# 02_Top_Level.net
KiCad netlist of a schematic drawn in Altium Designer
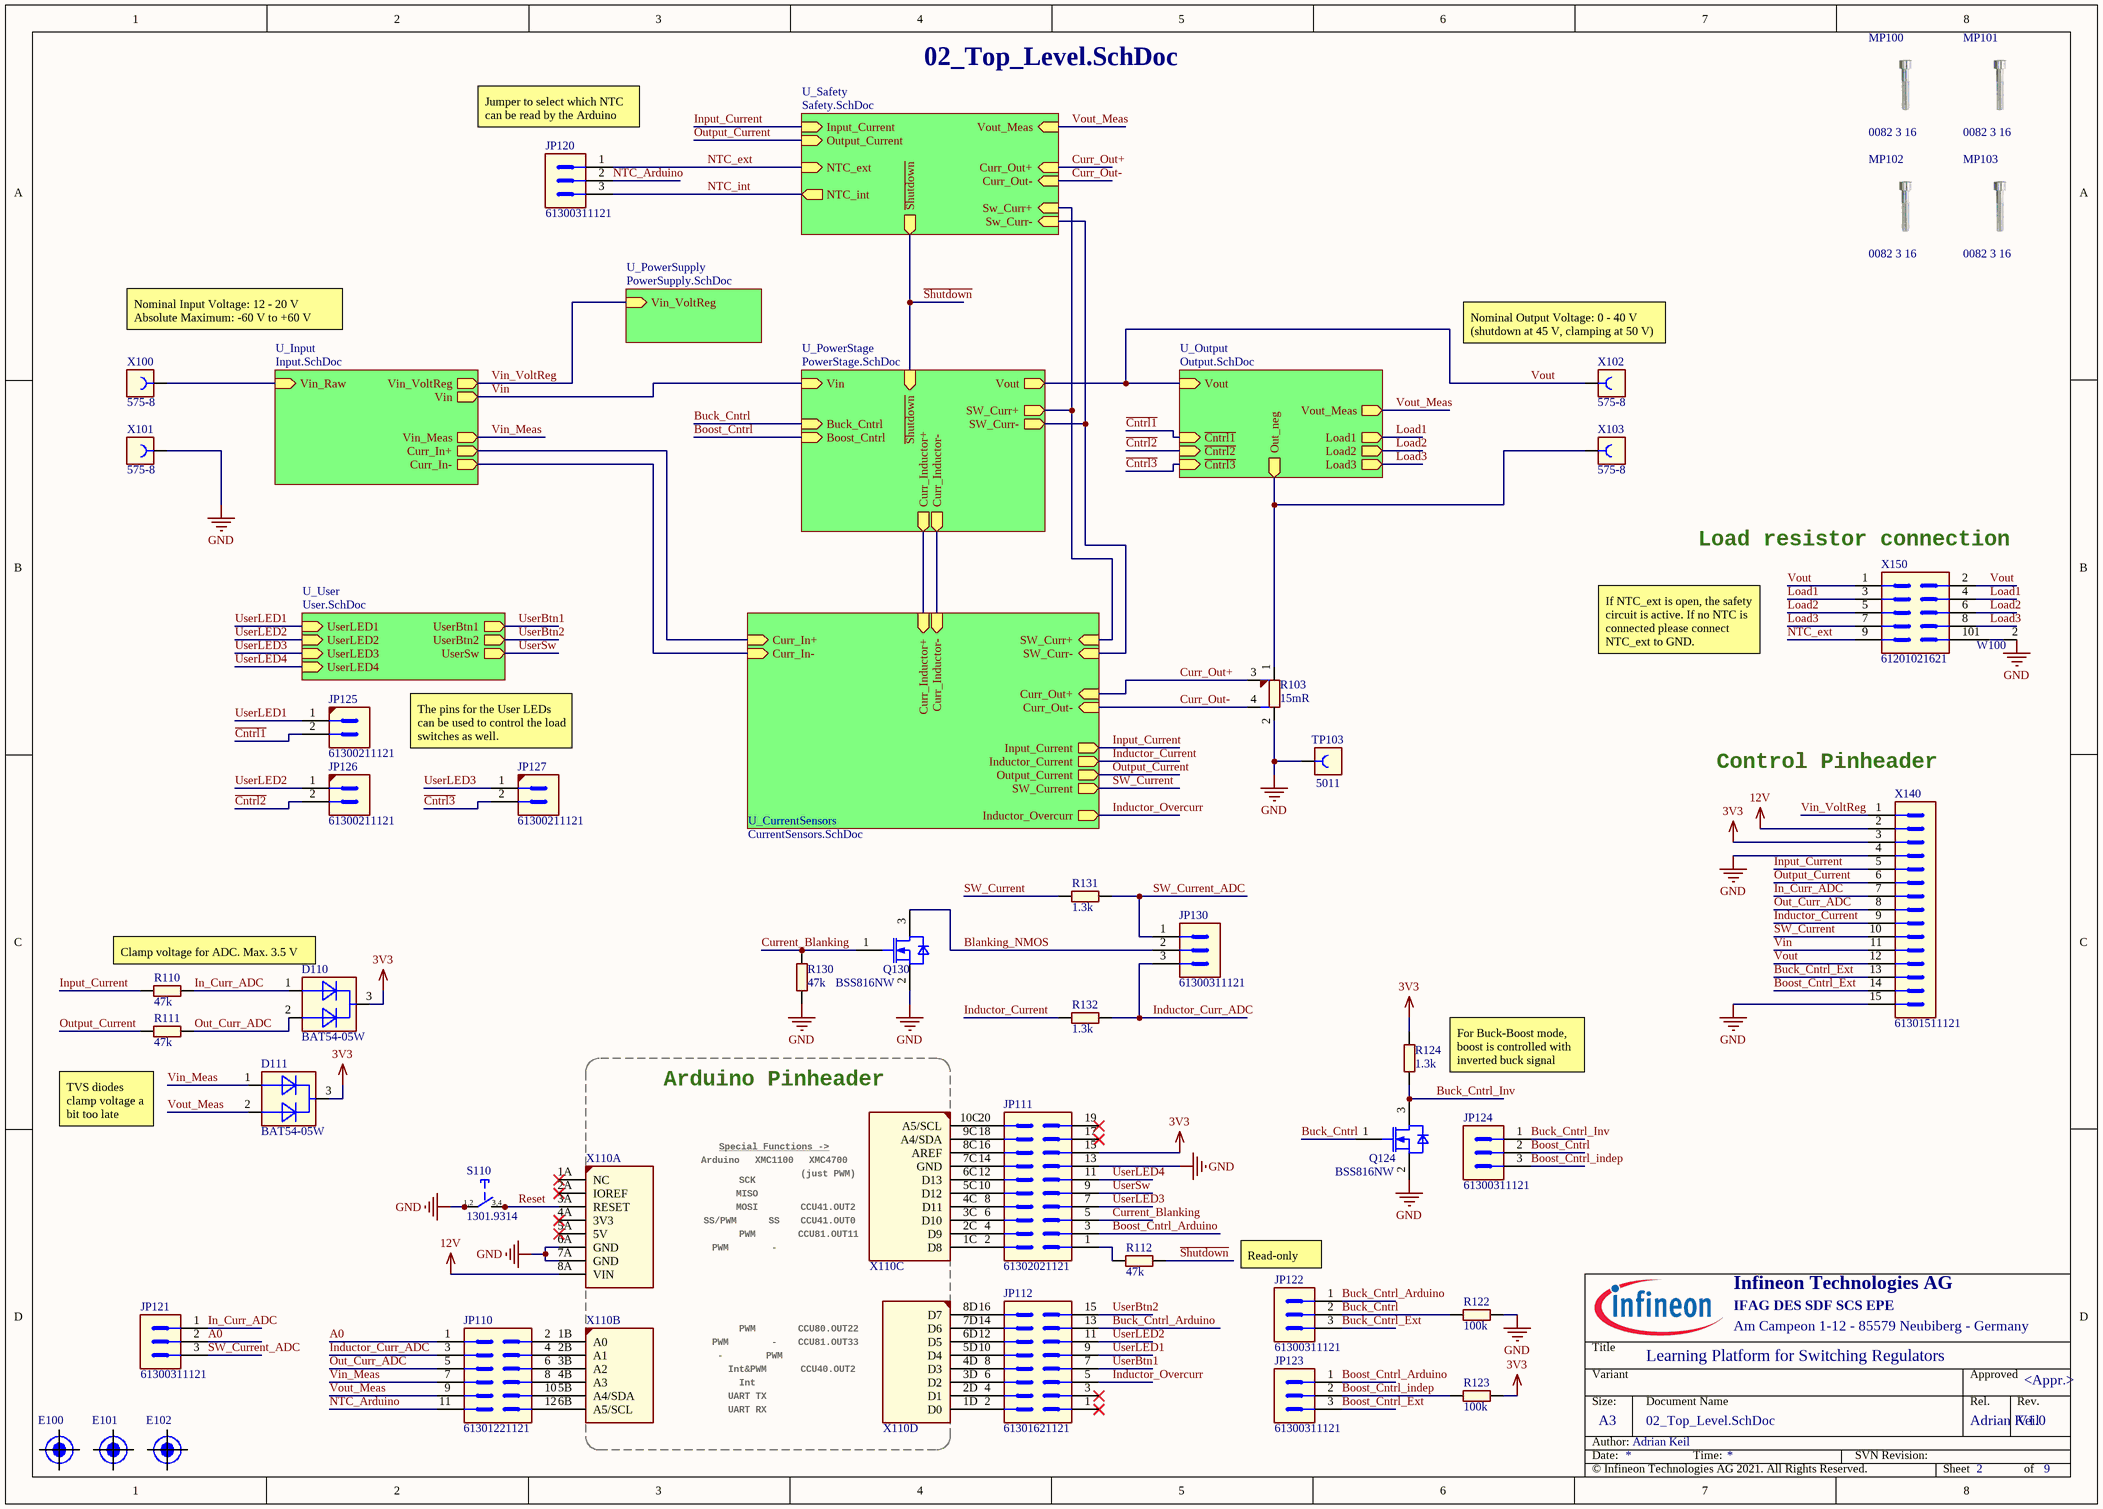
[diagram p0: 02_Top_Level.SchDoc]

(export (version "E")
  (design (tool "Eeschema 10.0.6"))
  (components
    (comp (ref "D110")
      (value "BAT54-05W")
      (footprint "SOT65P210X100-3N-1-V")
      (description "Silicon Schottky Diode, VR 30V")
      (fields (field (name "MANUFACTURER") "Infineon Technologies"))
      (libsource (lib "PCBLibraryData") (part "d_dual_a1a2c3_3p"))
    )
    (comp (ref "D111")
      (value "BAT54-05W")
      (footprint "SOT65P210X100-3N-1-V")
      (description "Silicon Schottky Diode, VR 30V")
      (fields (field (name "MANUFACTURER") "Infineon Technologies"))
      (libsource (lib "PCBLibraryData") (part "d_dual_a1a2c3_3p"))
    )
    (comp (ref "E100")
      (value "~")
      (footprint "fiducial")
      (description "Fiducial Mark")
      (fields
        (field (name "LEGACY PARTNUMBER") "MEC10000008")
        (field (name "MANUFACTURER") "Infineon Technologies")
      )
      (libsource (lib "PCBLibraryData") (part "fiducial"))
    )
    (comp (ref "E101")
      (value "~")
      (footprint "fiducial")
      (description "Fiducial Mark")
      (fields
        (field (name "LEGACY PARTNUMBER") "MEC10000008")
        (field (name "MANUFACTURER") "Infineon Technologies")
      )
      (libsource (lib "PCBLibraryData") (part "fiducial"))
    )
    (comp (ref "E102")
      (value "~")
      (footprint "fiducial")
      (description "Fiducial Mark")
      (fields
        (field (name "LEGACY PARTNUMBER") "MEC10000008")
        (field (name "MANUFACTURER") "Infineon Technologies")
      )
      (libsource (lib "PCBLibraryData") (part "fiducial"))
    )
    (comp (ref "JP110")
      (value "61301221121")
      (footprint "CON-M-THT-61301221121")
      (description "WR-PHD Dual Pin Header, 2.54mm Pitch, Double row, 12 Pins")
      (fields (field (name "MANUFACTURER") "Wurth Elektronik"))
      (libsource (lib "PCBLibraryData") (part "Header 6x2"))
    )
    (comp (ref "JP111")
      (value "61302021121")
      (footprint "CON-M-THT-61302021121")
      (description "WR-PHD Dual Pin Header, 2.54mm Pitch, Double row, 20 Pins")
      (fields (field (name "MANUFACTURER") "Wurth Elektronik"))
      (libsource (lib "PCBLibraryData") (part "Header 10X2"))
    )
    (comp (ref "JP112")
      (value "61301621121")
      (footprint "CON-M-THT-61301621121")
      (description "Connector Header Through Hole 16 position 0.100 (2.54mm)")
      (fields (field (name "MANUFACTURER") "Wurth Elektronik"))
      (libsource (lib "PCBLibraryData") (part "Header 8X2"))
    )
    (comp (ref "JP120")
      (value "61300311121")
      (footprint "CON-M-THT-61300311121")
      (description "WR-PHD Pin Header")
      (fields (field (name "MANUFACTURER") "Wurth Elektronik"))
      (libsource (lib "PCBLibraryData") (part "Header 3"))
    )
    (comp (ref "JP121")
      (value "61300311121")
      (footprint "CON-M-THT-61300311121")
      (description "WR-PHD Pin Header")
      (fields (field (name "MANUFACTURER") "Wurth Elektronik"))
      (libsource (lib "PCBLibraryData") (part "Header 3"))
    )
    (comp (ref "JP122")
      (value "61300311121")
      (footprint "CON-M-THT-61300311121")
      (description "WR-PHD Pin Header")
      (fields (field (name "MANUFACTURER") "Wurth Elektronik"))
      (libsource (lib "PCBLibraryData") (part "Header 3"))
    )
    (comp (ref "JP123")
      (value "61300311121")
      (footprint "CON-M-THT-61300311121")
      (description "WR-PHD Pin Header")
      (fields (field (name "MANUFACTURER") "Wurth Elektronik"))
      (libsource (lib "PCBLibraryData") (part "Header 3"))
    )
    (comp (ref "JP124")
      (value "61300311121")
      (footprint "CON-M-THT-61300311121")
      (description "WR-PHD Pin Header")
      (fields (field (name "MANUFACTURER") "Wurth Elektronik"))
      (libsource (lib "PCBLibraryData") (part "Header 3"))
    )
    (comp (ref "JP125")
      (value "61300211121")
      (footprint "CON-M-THT-61300211121")
      (description "Header, 2.54mm Pitch, 2 pin, Vertical, Single Row")
      (fields
        (field (name "LEGACY PARTNUMBER") "CON01500943")
        (field (name "MANUFACTURER") "Wurth Elektronik")
      )
      (libsource (lib "PCBLibraryData") (part "Header 2"))
    )
    (comp (ref "JP126")
      (value "61300211121")
      (footprint "CON-M-THT-61300211121")
      (description "Header, 2.54mm Pitch, 2 pin, Vertical, Single Row")
      (fields
        (field (name "LEGACY PARTNUMBER") "CON01500943")
        (field (name "MANUFACTURER") "Wurth Elektronik")
      )
      (libsource (lib "PCBLibraryData") (part "Header 2"))
    )
    (comp (ref "JP127")
      (value "61300211121")
      (footprint "CON-M-THT-61300211121")
      (description "Header, 2.54mm Pitch, 2 pin, Vertical, Single Row")
      (fields
        (field (name "LEGACY PARTNUMBER") "CON01500943")
        (field (name "MANUFACTURER") "Wurth Elektronik")
      )
      (libsource (lib "PCBLibraryData") (part "Header 2"))
    )
    (comp (ref "JP130")
      (value "61300311121")
      (footprint "CON-M-THT-61300311121")
      (description "WR-PHD Pin Header")
      (fields (field (name "MANUFACTURER") "Wurth Elektronik"))
      (libsource (lib "") (part "Header 3_1"))
    )
    (comp (ref "MP100")
      (value "0082 3 16")
      (footprint "SCREW_0082 3 16_NPTH")
      (description "Cheese Head Screw With Hexagon Socket, DIN 912 (ISO 4762), M3, 16mm length")
      (fields
        (field (name "LEGACY PARTNUMBER") "MEC10000167")
        (field (name "MANUFACTURER") "Wurth Elektronik")
      )
      (libsource (lib "PCBLibraryData") (part "Screw_0082 3 16"))
    )
    (comp (ref "MP101")
      (value "0082 3 16")
      (footprint "SCREW_0082 3 16_NPTH")
      (description "Cheese Head Screw With Hexagon Socket, DIN 912 (ISO 4762), M3, 16mm length")
      (fields
        (field (name "LEGACY PARTNUMBER") "MEC10000167")
        (field (name "MANUFACTURER") "Wurth Elektronik")
      )
      (libsource (lib "PCBLibraryData") (part "Screw_0082 3 16"))
    )
    (comp (ref "MP102")
      (value "0082 3 16")
      (footprint "SCREW_0082 3 16_NPTH")
      (description "Cheese Head Screw With Hexagon Socket, DIN 912 (ISO 4762), M3, 16mm length")
      (fields
        (field (name "LEGACY PARTNUMBER") "MEC10000167")
        (field (name "MANUFACTURER") "Wurth Elektronik")
      )
      (libsource (lib "PCBLibraryData") (part "Screw_0082 3 16"))
    )
    (comp (ref "MP103")
      (value "0082 3 16")
      (footprint "SCREW_0082 3 16_NPTH")
      (description "Cheese Head Screw With Hexagon Socket, DIN 912 (ISO 4762), M3, 16mm length")
      (fields
        (field (name "LEGACY PARTNUMBER") "MEC10000167")
        (field (name "MANUFACTURER") "Wurth Elektronik")
      )
      (libsource (lib "PCBLibraryData") (part "Screw_0082 3 16"))
    )
    (comp (ref "Q124")
      (value "BSS816NW")
      (footprint "SOT65P210X100-3N-1-V")
      (description "OptiMOS 2 Small-Signal-Transistor")
      (fields (field (name "MANUFACTURER") "Infineon Technologies"))
      (libsource (lib "PCBLibraryData") (part "igfet_n_ch_dep_dio_1g2s3d_3p"))
    )
    (comp (ref "Q130")
      (value "BSS816NW")
      (footprint "SOT65P210X100-3N-1-V")
      (description "OptiMOS 2 Small-Signal-Transistor")
      (fields (field (name "MANUFACTURER") "Infineon Technologies"))
      (libsource (lib "PCBLibraryData") (part "igfet_n_ch_dep_dio_1g2s3d_3p"))
    )
    (comp (ref "R103")
      (value "15mR")
      (footprint "RES-SMD-L4T12")
      (description "RES / STD / 15mR / 500mW / 1% / 75ppm/K / -55°C to 155°C / 1206 (3216) / SMD / -")
      (fields (field (name "MANUFACTURER") "Ohmite"))
      (libsource (lib "PCBLibraryData") (part "RES-SHT-STD-04P_00097BE5"))
    )
    (comp (ref "R110")
      (value "47k")
      (footprint "RESC1609X50N")
      (description "RES / STD / 47k / 100mW / 1% / 100ppm/K / -55°C to 155°C / 0603 / SMD / -")
      (fields (field (name "LEGACY PARTNUMBER") "RES01801333") (field (name "MANUFACTURER") "Vishay"))
      (libsource (lib "PCBLibraryData") (part "RES-SGL-STD-02P_00000006"))
    )
    (comp (ref "R111")
      (value "47k")
      (footprint "RESC1609X50N")
      (description "RES / STD / 47k / 100mW / 1% / 100ppm/K / -55°C to 155°C / 0603 / SMD / -")
      (fields (field (name "LEGACY PARTNUMBER") "RES01801333") (field (name "MANUFACTURER") "Vishay"))
      (libsource (lib "PCBLibraryData") (part "RES-SGL-STD-02P_00000006"))
    )
    (comp (ref "R112")
      (value "47k")
      (footprint "RESC1609X50N")
      (description "RES / STD / 47k / 100mW / 1% / 100ppm/K / -55°C to 155°C / 0603 / SMD / -")
      (fields (field (name "LEGACY PARTNUMBER") "RES01801333") (field (name "MANUFACTURER") "Vishay"))
      (libsource (lib "PCBLibraryData") (part "RES-SGL-STD-02P_00000006"))
    )
    (comp (ref "R122")
      (value "100k")
      (footprint "RESC1609X50N")
      (description "RES / STD / 100k / 100mW / 1% / 100ppm/K / -55°C to 155°C / 0603 / SMD / -")
      (fields (field (name "LEGACY PARTNUMBER") "RES01801371") (field (name "MANUFACTURER") "Vishay"))
      (libsource (lib "PCBLibraryData") (part "RES-SGL-STD-02P_00000006"))
    )
    (comp (ref "R123")
      (value "100k")
      (footprint "RESC1609X50N")
      (description "RES / STD / 100k / 100mW / 1% / 100ppm/K / -55°C to 155°C / 0603 / SMD / -")
      (fields (field (name "LEGACY PARTNUMBER") "RES01801371") (field (name "MANUFACTURER") "Vishay"))
      (libsource (lib "PCBLibraryData") (part "RES-SGL-STD-02P_00000006"))
    )
    (comp (ref "R124")
      (value "1.3k")
      (footprint "RESC1609X50N")
      (description "RES / STD / 1.3k / 100mW / 1% / 100ppm/K / -55°C to 155°C / 0603 / SMD / -")
      (fields (field (name "LEGACY PARTNUMBER") "RES01801155") (field (name "MANUFACTURER") "Vishay"))
      (libsource (lib "") (part "RES-SGL-STD-02P_00000006_1"))
    )
    (comp (ref "R130")
      (value "47k")
      (footprint "RESC1609X50N")
      (description "RES / STD / 47k / 100mW / 1% / 100ppm/K / -55°C to 155°C / 0603 / SMD / -")
      (fields (field (name "LEGACY PARTNUMBER") "RES01801333") (field (name "MANUFACTURER") "Vishay"))
      (libsource (lib "") (part "RES-SGL-STD-02P_00000006_1"))
    )
    (comp (ref "R131")
      (value "1.3k")
      (footprint "RESC1609X50N")
      (description "RES / STD / 1.3k / 100mW / 1% / 100ppm/K / -55°C to 155°C / 0603 / SMD / -")
      (fields (field (name "LEGACY PARTNUMBER") "RES01801155") (field (name "MANUFACTURER") "Vishay"))
      (libsource (lib "PCBLibraryData") (part "RES-SGL-STD-02P_00000006"))
    )
    (comp (ref "R132")
      (value "1.3k")
      (footprint "RESC1609X50N")
      (description "RES / STD / 1.3k / 100mW / 1% / 100ppm/K / -55°C to 155°C / 0603 / SMD / -")
      (fields (field (name "LEGACY PARTNUMBER") "RES01801155") (field (name "MANUFACTURER") "Vishay"))
      (libsource (lib "PCBLibraryData") (part "RES-SGL-STD-02P_00000006"))
    )
    (comp (ref "S110")
      (value "1301.9314")
      (footprint "SW-SMD-1301.9314")
      (description "Pushbutton Tactile Switch, Single Pole Single Throw, 4 Pins")
      (fields (field (name "LEGACY PARTNUMBER") "CON01500305") (field (name "MANUFACTURER") "Schurter"))
      (libsource (lib "PCBLibraryData") (part "sw_sr_no12_34_4p"))
    )
    (comp (ref "TP103")
      (value "5011")
      (footprint "CON-THT-TP-5011")
      (description "PC Test Point-Multipurpose THT, Black")
      (fields
        (field (name "LEGACY PARTNUMBER") "CON01500530")
        (field (name "MANUFACTURER") "Keystone Electronics Corp.")
      )
      (libsource (lib "") (part "connector_1_f_1"))
    )
    (comp (ref "W100")
      (value "Net_Tie_2")
      (footprint "Net_Tie_Small_2P")
      (description "SMD Net Tie for two Nets")
      (fields
        (field (name "LEGACY PARTNUMBER") "CON01501379")
        (field (name "MANUFACTURER") "Infineon Technologies")
      )
      (libsource (lib "PCBLibraryData") (part "Net_Tie_2"))
    )
    (comp (ref "X100")
      (value "575-8")
      (footprint "CON-F-TH-575-6")
      (description "Non Insulated Jack, Brass")
      (fields (field (name "MANUFACTURER") "Keystone Electronics Corp."))
      (libsource (lib "PCBLibraryData") (part "connector_1_f"))
    )
    (comp (ref "X101")
      (value "575-8")
      (footprint "CON-F-TH-575-6")
      (description "Non Insulated Jack, Brass")
      (fields (field (name "MANUFACTURER") "Keystone Electronics Corp."))
      (libsource (lib "PCBLibraryData") (part "connector_1_f"))
    )
    (comp (ref "X102")
      (value "575-8")
      (footprint "CON-F-TH-575-6")
      (description "Non Insulated Jack, Brass")
      (fields (field (name "MANUFACTURER") "Keystone Electronics Corp."))
      (libsource (lib "") (part "connector_1_f_2"))
    )
    (comp (ref "X103")
      (value "575-8")
      (footprint "CON-F-TH-575-6")
      (description "Non Insulated Jack, Brass")
      (fields (field (name "MANUFACTURER") "Keystone Electronics Corp."))
      (libsource (lib "") (part "connector_1_f_2"))
    )
    (comp (ref "X110")
      (value "Arduino-Uno")
      (footprint "Arduino-Uno")
      (description "Arduino Uno is a microcontroller board based on the ATmega328P")
      (fields (field (name "MANUFACTURER") "Infineon Technologies"))
      (libsource (lib "") (part "Arduino-Uno_1"))
    )
    (comp (ref "X140")
      (value "61301511121")
      (footprint "CON-M-THT-61301511121")
      (description "WR-PHD Pin Header, 2.54mm Pitch, Single row, 15 Pins")
      (fields (field (name "MANUFACTURER") "Wurth Elektronik"))
      (libsource (lib "PCBLibraryData") (part "Header 15"))
    )
    (comp (ref "X150")
      (value "61201021621")
      (footprint "CON-M-THT-61201021621")
      (description "WR-BHD Male Box Header, 2.54mm pitch, 10 pin, Vertical, Double row")
      (fields (field (name "MANUFACTURER") "Wurth Elektronik"))
      (libsource (lib "PCBLibraryData") (part "Header 5X2"))
    )
  )
  (nets
    (net (code "1") (name "/A0") (class "Default")
      (node (ref "JP110") (pin "1") (pinfunction "1_1") (pintype "passive"))
      (node (ref "JP121") (pin "2") (pinfunction "2_2") (pintype "passive"))
    )
    (net (code "2") (name "/Blanking_NMOS") (class "Default")
      (node (ref "JP130") (pin "2") (pinfunction "2_2") (pintype "passive"))
      (node (ref "Q130") (pin "3") (pinfunction "DRAIN_3") (pintype "passive"))
    )
    (net (code "3") (name "/Boost_Cntrl") (class "Default")
      (node (ref "JP124") (pin "2") (pinfunction "2_2") (pintype "passive"))
    )
    (net (code "4") (name "/Boost_Cntrl_Arduino") (class "Default")
      (node (ref "JP111") (pin "3") (pinfunction "3_3") (pintype "passive"))
      (node (ref "JP123") (pin "1") (pinfunction "1_1") (pintype "passive"))
    )
    (net (code "5") (name "/Boost_Cntrl_Ext") (class "Default")
      (node (ref "JP123") (pin "3") (pinfunction "3_3") (pintype "passive"))
      (node (ref "X140") (pin "14") (pinfunction "14_14") (pintype "passive"))
    )
    (net (code "6") (name "/Boost_Cntrl_indep") (class "Default")
      (node (ref "JP123") (pin "2") (pinfunction "2_2") (pintype "passive"))
      (node (ref "JP124") (pin "3") (pinfunction "3_3") (pintype "passive"))
      (node (ref "R123") (pin "2") (pinfunction "2_2") (pintype "passive"))
    )
    (net (code "7") (name "/Buck_Cntrl") (class "Default")
      (node (ref "JP122") (pin "2") (pinfunction "2_2") (pintype "passive"))
      (node (ref "Q124") (pin "1") (pinfunction "GATE_1") (pintype "passive"))
      (node (ref "R122") (pin "2") (pinfunction "2_2") (pintype "passive"))
    )
    (net (code "8") (name "/Buck_Cntrl_Arduino") (class "Default")
      (node (ref "JP112") (pin "13") (pinfunction "13_13") (pintype "passive"))
      (node (ref "JP122") (pin "1") (pinfunction "1_1") (pintype "passive"))
    )
    (net (code "9") (name "/Buck_Cntrl_Ext") (class "Default")
      (node (ref "JP122") (pin "3") (pinfunction "3_3") (pintype "passive"))
      (node (ref "X140") (pin "13") (pinfunction "13_13") (pintype "passive"))
    )
    (net (code "10") (name "/Buck_Cntrl_Inv") (class "Default")
      (node (ref "JP124") (pin "1") (pinfunction "1_1") (pintype "passive"))
      (node (ref "Q124") (pin "3") (pinfunction "DRAIN_3") (pintype "passive"))
      (node (ref "R124") (pin "1") (pinfunction "1_1") (pintype "passive"))
    )
    (net (code "11") (name "/Cntrl1") (class "Default")
      (node (ref "JP125") (pin "2") (pinfunction "2_2") (pintype "passive"))
    )
    (net (code "12") (name "/Cntrl2") (class "Default")
      (node (ref "JP126") (pin "2") (pinfunction "2_2") (pintype "passive"))
    )
    (net (code "13") (name "/Cntrl3") (class "Default")
      (node (ref "JP127") (pin "2") (pinfunction "2_2") (pintype "passive"))
    )
    (net (code "18") (name "/Curr_Out+") (class "Default")
      (node (ref "R103") (pin "3") (pinfunction "I1_3") (pintype "passive"))
    )
    (net (code "19") (name "/Curr_Out-") (class "Default")
      (node (ref "R103") (pin "4") (pinfunction "I2_4") (pintype "passive"))
    )
    (net (code "20") (name "/Current_Blanking") (class "Default")
      (node (ref "JP111") (pin "5") (pinfunction "5_5") (pintype "passive"))
      (node (ref "Q130") (pin "1") (pinfunction "GATE_1") (pintype "passive"))
      (node (ref "R130") (pin "2") (pinfunction "2_2") (pintype "passive"))
    )
    (net (code "21") (name "/In_Curr_ADC") (class "Default")
      (node (ref "D110") (pin "1") (pinfunction "ANODE_1_1") (pintype "passive"))
      (node (ref "JP121") (pin "1") (pinfunction "1_1") (pintype "passive"))
      (node (ref "R110") (pin "1") (pinfunction "1_1") (pintype "passive"))
      (node (ref "X140") (pin "7") (pinfunction "7_7") (pintype "passive"))
    )
    (net (code "22") (name "/Inductor_Curr_ADC") (class "Default")
      (node (ref "JP110") (pin "3") (pinfunction "3_3") (pintype "passive"))
      (node (ref "JP130") (pin "3") (pinfunction "3_3") (pintype "passive"))
      (node (ref "R132") (pin "1") (pinfunction "1_1") (pintype "passive"))
    )
    (net (code "23") (name "/Inductor_Current") (class "Default")
      (node (ref "R132") (pin "2") (pinfunction "2_2") (pintype "passive"))
      (node (ref "X140") (pin "9") (pinfunction "9_9") (pintype "passive"))
    )
    (net (code "24") (name "/Inductor_Overcurr") (class "Default")
      (node (ref "JP112") (pin "5") (pinfunction "5_5") (pintype "passive"))
    )
    (net (code "25") (name "/Input_Current") (class "Default")
      (node (ref "R110") (pin "2") (pinfunction "2_2") (pintype "passive"))
      (node (ref "X140") (pin "5") (pinfunction "5_5") (pintype "passive"))
    )
    (net (code "26") (name "/Load1") (class "Default")
      (node (ref "X150") (pin "3") (pinfunction "3_3") (pintype "passive"))
      (node (ref "X150") (pin "4") (pinfunction "4_4") (pintype "passive"))
    )
    (net (code "27") (name "/Load2") (class "Default")
      (node (ref "X150") (pin "5") (pinfunction "5_5") (pintype "passive"))
      (node (ref "X150") (pin "6") (pinfunction "6_6") (pintype "passive"))
    )
    (net (code "28") (name "/Load3") (class "Default")
      (node (ref "X150") (pin "7") (pinfunction "7_7") (pintype "passive"))
      (node (ref "X150") (pin "8") (pinfunction "8_8") (pintype "passive"))
    )
    (net (code "29") (name "/NTC_Arduino") (class "Default")
      (node (ref "JP110") (pin "11") (pinfunction "11_11") (pintype "passive"))
      (node (ref "JP120") (pin "2") (pinfunction "2_2") (pintype "passive"))
    )
    (net (code "30") (name "/NTC_ext") (class "Default")
      (node (ref "JP120") (pin "1") (pinfunction "1_1") (pintype "passive"))
      (node (ref "X150") (pin "9") (pinfunction "9_9") (pintype "passive"))
    )
    (net (code "31") (name "/NTC_int") (class "Default")
      (node (ref "JP120") (pin "3") (pinfunction "3_3") (pintype "passive"))
    )
    (net (code "32") (name "/Out_Curr_ADC") (class "Default")
      (node (ref "D110") (pin "2") (pinfunction "ANODE_2_2") (pintype "passive"))
      (node (ref "JP110") (pin "5") (pinfunction "5_5") (pintype "passive"))
      (node (ref "R111") (pin "1") (pinfunction "1_1") (pintype "passive"))
      (node (ref "X140") (pin "8") (pinfunction "8_8") (pintype "passive"))
    )
    (net (code "33") (name "/Out_neg") (class "Default")
      (node (ref "R103") (pin "1") (pinfunction "V1_1") (pintype "passive"))
      (node (ref "X103") (pin "1") (pinfunction "1_1") (pintype "passive"))
    )
    (net (code "34") (name "/Output_Current") (class "Default")
      (node (ref "R111") (pin "2") (pinfunction "2_2") (pintype "passive"))
      (node (ref "X140") (pin "6") (pinfunction "6_6") (pintype "passive"))
    )
    (net (code "35") (name "/Reset") (class "Default")
      (node (ref "S110") (pin "3") (pinfunction "3_3") (pintype "passive"))
      (node (ref "S110") (pin "4") (pinfunction "4_4") (pintype "passive"))
      (node (ref "X110") (pin "3A") (pinfunction "RESET_3A") (pintype "passive"))
    )
    (net (code "38") (name "/SW_Current") (class "Default")
      (node (ref "R131") (pin "2") (pinfunction "2_2") (pintype "passive"))
      (node (ref "X140") (pin "10") (pinfunction "10_10") (pintype "passive"))
    )
    (net (code "39") (name "/SW_Current_ADC") (class "Default")
      (node (ref "JP121") (pin "3") (pinfunction "3_3") (pintype "passive"))
      (node (ref "JP130") (pin "1") (pinfunction "1_1") (pintype "passive"))
      (node (ref "R131") (pin "1") (pinfunction "1_1") (pintype "passive"))
    )
    (net (code "40") (name "/Shutdown") (class "Default")
      (node (ref "R112") (pin "1") (pinfunction "1_1") (pintype "passive"))
    )
    (net (code "41") (name "/UserBtn1") (class "Default")
      (node (ref "JP112") (pin "7") (pinfunction "7_7") (pintype "passive"))
    )
    (net (code "42") (name "/UserBtn2") (class "Default")
      (node (ref "JP112") (pin "15") (pinfunction "15_15") (pintype "passive"))
    )
    (net (code "43") (name "/UserLED1") (class "Default")
      (node (ref "JP112") (pin "9") (pinfunction "9_9") (pintype "passive"))
      (node (ref "JP125") (pin "1") (pinfunction "1_1") (pintype "passive"))
    )
    (net (code "44") (name "/UserLED2") (class "Default")
      (node (ref "JP112") (pin "11") (pinfunction "11_11") (pintype "passive"))
      (node (ref "JP126") (pin "1") (pinfunction "1_1") (pintype "passive"))
    )
    (net (code "45") (name "/UserLED3") (class "Default")
      (node (ref "JP111") (pin "7") (pinfunction "7_7") (pintype "passive"))
      (node (ref "JP127") (pin "1") (pinfunction "1_1") (pintype "passive"))
    )
    (net (code "46") (name "/UserLED4") (class "Default")
      (node (ref "JP111") (pin "11") (pinfunction "11_11") (pintype "passive"))
    )
    (net (code "47") (name "/UserSw") (class "Default")
      (node (ref "JP111") (pin "9") (pinfunction "9_9") (pintype "passive"))
    )
    (net (code "48") (name "/Vin") (class "Default")
      (node (ref "X140") (pin "11") (pinfunction "11_11") (pintype "passive"))
    )
    (net (code "49") (name "/Vin_Meas") (class "Default")
      (node (ref "D111") (pin "1") (pinfunction "ANODE_1_1") (pintype "passive"))
      (node (ref "JP110") (pin "7") (pinfunction "7_7") (pintype "passive"))
    )
    (net (code "50") (name "/Vin_Raw") (class "Default")
      (node (ref "X100") (pin "1") (pinfunction "1_1") (pintype "passive"))
    )
    (net (code "51") (name "/Vin_VoltReg") (class "Default")
      (node (ref "X140") (pin "1") (pinfunction "1_1") (pintype "passive"))
    )
    (net (code "52") (name "/Vout") (class "Default")
      (node (ref "X102") (pin "1") (pinfunction "1_1") (pintype "passive"))
      (node (ref "X140") (pin "12") (pinfunction "12_12") (pintype "passive"))
      (node (ref "X150") (pin "1") (pinfunction "1_1") (pintype "passive"))
      (node (ref "X150") (pin "2") (pinfunction "2_2") (pintype "passive"))
    )
    (net (code "53") (name "/Vout_Meas") (class "Default")
      (node (ref "D111") (pin "2") (pinfunction "ANODE_2_2") (pintype "passive"))
      (node (ref "JP110") (pin "9") (pinfunction "9_9") (pintype "passive"))
    )
    (net (code "54") (name "3V3") (class "Default")
      (node (ref "D110") (pin "3") (pinfunction "CATHODE_3") (pintype "passive"))
      (node (ref "D111") (pin "3") (pinfunction "CATHODE_3") (pintype "passive"))
      (node (ref "JP111") (pin "15") (pinfunction "15_15") (pintype "passive"))
      (node (ref "R123") (pin "1") (pinfunction "1_1") (pintype "passive"))
      (node (ref "R124") (pin "2") (pinfunction "2_2") (pintype "passive"))
      (node (ref "X140") (pin "3") (pinfunction "3_3") (pintype "passive"))
    )
    (net (code "55") (name "12V") (class "Default")
      (node (ref "X110") (pin "8A") (pinfunction "VIN_8A") (pintype "passive"))
      (node (ref "X140") (pin "2") (pinfunction "2_2") (pintype "passive"))
    )
    (net (code "56") (name "GND") (class "Default")
      (node (ref "JP111") (pin "13") (pinfunction "13_13") (pintype "passive"))
      (node (ref "Q124") (pin "2") (pinfunction "SOURCE_2") (pintype "passive"))
      (node (ref "Q130") (pin "2") (pinfunction "SOURCE_2") (pintype "passive"))
      (node (ref "R103") (pin "2") (pinfunction "V2_2") (pintype "passive"))
      (node (ref "R122") (pin "1") (pinfunction "1_1") (pintype "passive"))
      (node (ref "R130") (pin "1") (pinfunction "1_1") (pintype "passive"))
      (node (ref "S110") (pin "1") (pinfunction "1_1") (pintype "passive"))
      (node (ref "S110") (pin "2") (pinfunction "2_2") (pintype "passive"))
      (node (ref "TP103") (pin "1") (pinfunction "1_1") (pintype "passive"))
      (node (ref "W100") (pin "2") (pinfunction "2_2") (pintype "passive"))
      (node (ref "X101") (pin "1") (pinfunction "1_1") (pintype "passive"))
      (node (ref "X110") (pin "6A") (pinfunction "GND_6A") (pintype "passive"))
      (node (ref "X110") (pin "7A") (pinfunction "GND_7A") (pintype "passive"))
      (node (ref "X140") (pin "15") (pinfunction "15_15") (pintype "passive"))
      (node (ref "X140") (pin "4") (pinfunction "4_4") (pintype "passive"))
    )
    (net (code "57") (name "Net-(JP111-Pad1)") (class "Default")
      (node (ref "JP111") (pin "1") (pinfunction "1_1") (pintype "passive"))
      (node (ref "R112") (pin "2") (pinfunction "2_2") (pintype "passive"))
    )
    (net (code "58") (name "Net-(W100-Pad1)") (class "Default")
      (node (ref "W100") (pin "1") (pinfunction "1_1") (pintype "passive"))
      (node (ref "X150") (pin "10") (pinfunction "10_10") (pintype "passive"))
    )
    (net (code "59") (name "Net-(X110B-A0)") (class "Default")
      (node (ref "JP110") (pin "2") (pinfunction "2_2") (pintype "passive"))
      (node (ref "X110") (pin "1B") (pinfunction "A0_1B") (pintype "passive"))
    )
    (net (code "60") (name "Net-(X110B-A1)") (class "Default")
      (node (ref "JP110") (pin "4") (pinfunction "4_4") (pintype "passive"))
      (node (ref "X110") (pin "2B") (pinfunction "A1_2B") (pintype "passive"))
    )
    (net (code "61") (name "Net-(X110B-A2)") (class "Default")
      (node (ref "JP110") (pin "6") (pinfunction "6_6") (pintype "passive"))
      (node (ref "X110") (pin "3B") (pinfunction "A2_3B") (pintype "passive"))
    )
    (net (code "62") (name "Net-(X110B-A3)") (class "Default")
      (node (ref "JP110") (pin "8") (pinfunction "8_8") (pintype "passive"))
      (node (ref "X110") (pin "4B") (pinfunction "A3_4B") (pintype "passive"))
    )
    (net (code "63") (name "Net-(X110B-A4{slash}SDA)") (class "Default")
      (node (ref "JP110") (pin "10") (pinfunction "10_10") (pintype "passive"))
      (node (ref "X110") (pin "5B") (pinfunction "A4/SDA_5B") (pintype "passive"))
    )
    (net (code "64") (name "Net-(X110B-A5{slash}SCL)") (class "Default")
      (node (ref "JP110") (pin "12") (pinfunction "12_12") (pintype "passive"))
      (node (ref "X110") (pin "6B") (pinfunction "A5/SCL_6B") (pintype "passive"))
    )
    (net (code "65") (name "Net-(X110C-A4{slash}SDA)") (class "Default")
      (node (ref "JP111") (pin "18") (pinfunction "18_18") (pintype "passive"))
      (node (ref "X110") (pin "9C") (pinfunction "A4/SDA_9C") (pintype "passive"))
    )
    (net (code "66") (name "Net-(X110C-A5{slash}SCL)") (class "Default")
      (node (ref "JP111") (pin "20") (pinfunction "20_20") (pintype "passive"))
      (node (ref "X110") (pin "10C") (pinfunction "A5/SCL_10C") (pintype "passive"))
    )
    (net (code "67") (name "Net-(X110C-AREF)") (class "Default")
      (node (ref "JP111") (pin "16") (pinfunction "16_16") (pintype "passive"))
      (node (ref "X110") (pin "8C") (pinfunction "AREF_8C") (pintype "passive"))
    )
    (net (code "68") (name "Net-(X110C-D8)") (class "Default")
      (node (ref "JP111") (pin "2") (pinfunction "2_2") (pintype "passive"))
      (node (ref "X110") (pin "1C") (pinfunction "D8_1C") (pintype "passive"))
    )
    (net (code "69") (name "Net-(X110C-D9)") (class "Default")
      (node (ref "JP111") (pin "4") (pinfunction "4_4") (pintype "passive"))
      (node (ref "X110") (pin "2C") (pinfunction "D9_2C") (pintype "passive"))
    )
    (net (code "70") (name "Net-(X110C-D10)") (class "Default")
      (node (ref "JP111") (pin "6") (pinfunction "6_6") (pintype "passive"))
      (node (ref "X110") (pin "3C") (pinfunction "D10_3C") (pintype "passive"))
    )
    (net (code "71") (name "Net-(X110C-D11)") (class "Default")
      (node (ref "JP111") (pin "8") (pinfunction "8_8") (pintype "passive"))
      (node (ref "X110") (pin "4C") (pinfunction "D11_4C") (pintype "passive"))
    )
    (net (code "72") (name "Net-(X110C-D12)") (class "Default")
      (node (ref "JP111") (pin "10") (pinfunction "10_10") (pintype "passive"))
      (node (ref "X110") (pin "5C") (pinfunction "D12_5C") (pintype "passive"))
    )
    (net (code "73") (name "Net-(X110C-D13)") (class "Default")
      (node (ref "JP111") (pin "12") (pinfunction "12_12") (pintype "passive"))
      (node (ref "X110") (pin "6C") (pinfunction "D13_6C") (pintype "passive"))
    )
    (net (code "74") (name "Net-(X110C-GND)") (class "Default")
      (node (ref "JP111") (pin "14") (pinfunction "14_14") (pintype "passive"))
      (node (ref "X110") (pin "7C") (pinfunction "GND_7C") (pintype "passive"))
    )
    (net (code "75") (name "Net-(X110D-D0)") (class "Default")
      (node (ref "JP112") (pin "2") (pinfunction "2_2") (pintype "passive"))
      (node (ref "X110") (pin "1D") (pinfunction "D0_1D") (pintype "passive"))
    )
    (net (code "76") (name "Net-(X110D-D1)") (class "Default")
      (node (ref "JP112") (pin "4") (pinfunction "4_4") (pintype "passive"))
      (node (ref "X110") (pin "2D") (pinfunction "D1_2D") (pintype "passive"))
    )
    (net (code "77") (name "Net-(X110D-D2)") (class "Default")
      (node (ref "JP112") (pin "6") (pinfunction "6_6") (pintype "passive"))
      (node (ref "X110") (pin "3D") (pinfunction "D2_3D") (pintype "passive"))
    )
    (net (code "78") (name "Net-(X110D-D3)") (class "Default")
      (node (ref "JP112") (pin "8") (pinfunction "8_8") (pintype "passive"))
      (node (ref "X110") (pin "4D") (pinfunction "D3_4D") (pintype "passive"))
    )
    (net (code "79") (name "Net-(X110D-D4)") (class "Default")
      (node (ref "JP112") (pin "10") (pinfunction "10_10") (pintype "passive"))
      (node (ref "X110") (pin "5D") (pinfunction "D4_5D") (pintype "passive"))
    )
    (net (code "80") (name "Net-(X110D-D5)") (class "Default")
      (node (ref "JP112") (pin "12") (pinfunction "12_12") (pintype "passive"))
      (node (ref "X110") (pin "6D") (pinfunction "D5_6D") (pintype "passive"))
    )
    (net (code "81") (name "Net-(X110D-D6)") (class "Default")
      (node (ref "JP112") (pin "14") (pinfunction "14_14") (pintype "passive"))
      (node (ref "X110") (pin "7D") (pinfunction "D6_7D") (pintype "passive"))
    )
    (net (code "82") (name "Net-(X110D-D7)") (class "Default")
      (node (ref "JP112") (pin "16") (pinfunction "16_16") (pintype "passive"))
      (node (ref "X110") (pin "8D") (pinfunction "D7_8D") (pintype "passive"))
    )
    (net (code "83") (name "unconnected-(E100-Pad1)") (class "Default")
      (node (ref "E100") (pin "1") (pinfunction "1_1") (pintype "passive"))
    )
    (net (code "84") (name "unconnected-(E101-Pad1)") (class "Default")
      (node (ref "E101") (pin "1") (pinfunction "1_1") (pintype "passive"))
    )
    (net (code "85") (name "unconnected-(E102-Pad1)") (class "Default")
      (node (ref "E102") (pin "1") (pinfunction "1_1") (pintype "passive"))
    )
    (net (code "86") (name "unconnected-(JP111-Pad17)") (class "Default")
      (node (ref "JP111") (pin "17") (pinfunction "17_17") (pintype "passive+no_connect"))
    )
    (net (code "87") (name "unconnected-(JP111-Pad19)") (class "Default")
      (node (ref "JP111") (pin "19") (pinfunction "19_19") (pintype "passive+no_connect"))
    )
    (net (code "88") (name "unconnected-(JP112-Pad1)") (class "Default")
      (node (ref "JP112") (pin "1") (pinfunction "1_1") (pintype "passive+no_connect"))
    )
    (net (code "89") (name "unconnected-(JP112-Pad3)") (class "Default")
      (node (ref "JP112") (pin "3") (pinfunction "3_3") (pintype "passive+no_connect"))
    )
    (net (code "90") (name "unconnected-(X110A-3V3-Pad4A)") (class "Default")
      (node (ref "X110") (pin "4A") (pinfunction "3V3_4A") (pintype "passive+no_connect"))
    )
    (net (code "91") (name "unconnected-(X110A-5V-Pad5A)") (class "Default")
      (node (ref "X110") (pin "5A") (pinfunction "5V_5A") (pintype "passive+no_connect"))
    )
    (net (code "92") (name "unconnected-(X110A-IOREF-Pad2A)") (class "Default")
      (node (ref "X110") (pin "2A") (pinfunction "IOREF_2A") (pintype "passive+no_connect"))
    )
    (net (code "93") (name "unconnected-(X110A-NC-Pad1A)") (class "Default")
      (node (ref "X110") (pin "1A") (pinfunction "NC_1A") (pintype "passive+no_connect"))
    )
  )
)
